# Zigbee.net
KiCad netlist of a schematic drawn in Altium Designer
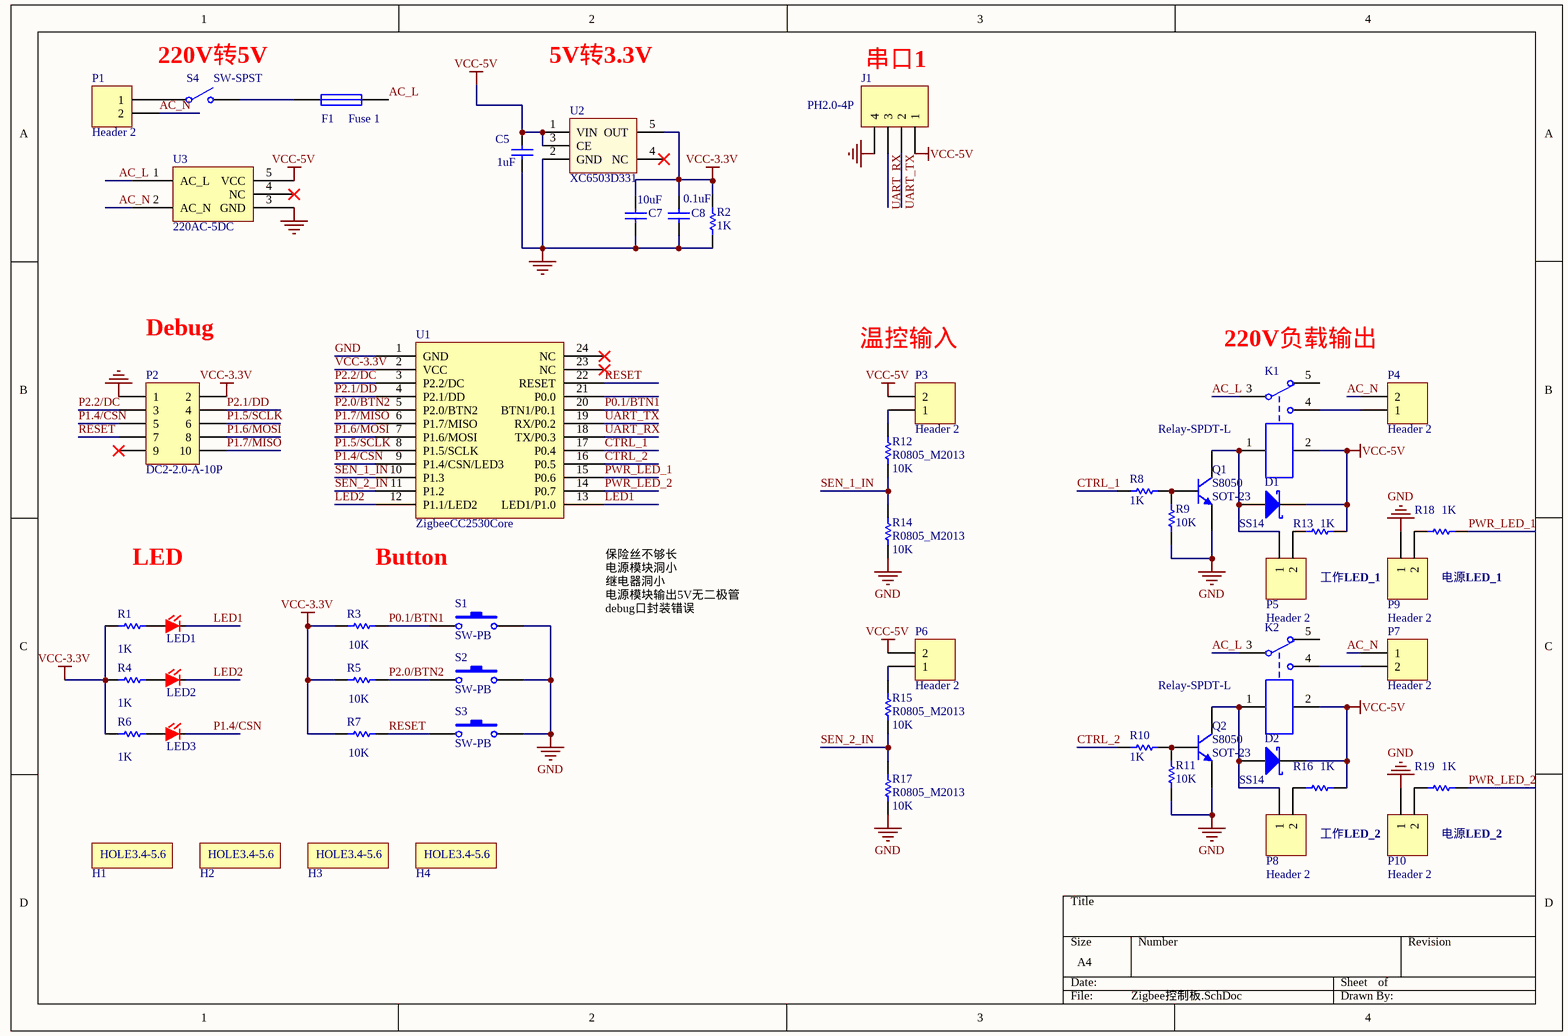
[diagram p0: Zigbee控制板.SchDoc]

(export (version "E")
  (design (tool "Eeschema 10.0.6"))
  (components
    (comp (ref "C5")
      (value "1uF")
      (footprint "C0805_M2013")
      (description "Capacitor")
      (fields (field (name "PUBLISHER") "Altium Limited"))
      (libsource (lib "Miscellaneous Devices") (part "Cap"))
    )
    (comp (ref "C7")
      (value "10uF")
      (footprint "C0805_M2013")
      (description "Capacitor")
      (fields (field (name "PUBLISHER") "Altium Limited"))
      (libsource (lib "Miscellaneous Devices") (part "Cap"))
    )
    (comp (ref "C8")
      (value "0.1uF")
      (footprint "C0805_M2013")
      (description "Capacitor")
      (fields (field (name "PUBLISHER") "Altium Limited"))
      (libsource (lib "Miscellaneous Devices") (part "Cap"))
    )
    (comp (ref "D1")
      (value "SS14")
      (footprint "SMA DO-214AC")
      (description "1.0 A Schottky Barrier Rectifiers")
      (fields (field (name "Comment") "SMA DO-214AC"))
      (libsource (lib "2.二极管原理库") (part "SS14"))
    )
    (comp (ref "D2")
      (value "SS14")
      (footprint "SMA DO-214AC")
      (description "1.0 A Schottky Barrier Rectifiers")
      (fields (field (name "Comment") "SMA DO-214AC"))
      (libsource (lib "2.二极管原理库") (part "SS14"))
    )
    (comp (ref "F1")
      (value "Fuse 1")
      (footprint "POLAR0.8")
      (description "Fuse")
      (fields (field (name "PUBLISHER") "Altium Limited"))
      (libsource (lib "Miscellaneous Devices") (part "Fuse 1"))
    )
    (comp (ref "H1")
      (value "HOLE3.4-5.6")
      (footprint "HOLE3.4-5.6")
      (libsource (lib "6.模块封装、Mark点、定位孔") (part "HOLE3.4-5.6"))
    )
    (comp (ref "H2")
      (value "HOLE3.4-5.6")
      (footprint "HOLE3.4-5.6")
      (libsource (lib "6.模块封装、Mark点、定位孔") (part "HOLE3.4-5.6"))
    )
    (comp (ref "H3")
      (value "HOLE3.4-5.6")
      (footprint "HOLE3.4-5.6")
      (libsource (lib "6.模块封装、Mark点、定位孔") (part "HOLE3.4-5.6"))
    )
    (comp (ref "H4")
      (value "HOLE3.4-5.6")
      (footprint "HOLE3.4-5.6")
      (libsource (lib "6.模块封装、Mark点、定位孔") (part "HOLE3.4-5.6"))
    )
    (comp (ref "J1")
      (value "PH2.0-4P")
      (footprint "PH2.0-4P")
      (description "Header, 4-Pin")
      (fields (field (name "PUBLISHER") "Altium Limited"))
      (libsource (lib "Miscellaneous Connectors") (part "Header 4"))
    )
    (comp (ref "K1")
      (value "Relay-SPDT-L")
      (footprint "Relay-SPDT-L")
      (description "Single-Pole Dual-Throw Relay")
      (fields (field (name "PUBLISHER") "Altium Limited"))
      (libsource (lib "Liyao原理图库") (part "Relay-SPDT-L"))
    )
    (comp (ref "K2")
      (value "Relay-SPDT-L")
      (footprint "Relay-SPDT-L")
      (description "Single-Pole Dual-Throw Relay")
      (fields (field (name "PUBLISHER") "Altium Limited"))
      (libsource (lib "Liyao原理图库") (part "Relay-SPDT-L"))
    )
    (comp (ref "LED1")
      (value "LED-R")
      (footprint "0805_LED")
      (description "LED红")
      (libsource (lib "Liyao原理图库") (part "LED-R"))
    )
    (comp (ref "LED2")
      (value "LED-R")
      (footprint "0805_LED")
      (description "LED红")
      (libsource (lib "Liyao原理图库") (part "LED-R"))
    )
    (comp (ref "LED3")
      (value "LED-R")
      (footprint "0805_LED")
      (description "LED红")
      (libsource (lib "Liyao原理图库") (part "LED-R"))
    )
    (comp (ref "P1")
      (value "Header 2")
      (footprint "KF301-2P")
      (description "Header, 2-Pin")
      (fields (field (name "PUBLISHER") "Altium Limited"))
      (libsource (lib "") (part "Header 2_3"))
    )
    (comp (ref "P2")
      (value "DC2-2.0-A-10P")
      (footprint "DC3-2.0-A-10P")
      (description "牛角座2.0 直插")
      (libsource (lib "8.其他连接器原理库") (part "DC2-2.0-A-10P"))
    )
    (comp (ref "P3")
      (value "Header 2")
      (footprint "HDR1X2")
      (description "Header, 2-Pin")
      (fields (field (name "PUBLISHER") "Altium Limited"))
      (libsource (lib "") (part "Header 2_1"))
    )
    (comp (ref "P4")
      (value "Header 2")
      (footprint "KF301-2P")
      (description "Header, 2-Pin")
      (fields (field (name "PUBLISHER") "Altium Limited"))
      (libsource (lib "") (part "Header 2_1"))
    )
    (comp (ref "P5")
      (value "Header 2")
      (footprint "HDR1X2")
      (description "Header, 2-Pin")
      (fields (field (name "PUBLISHER") "Altium Limited"))
      (libsource (lib "Miscellaneous Connectors") (part "Header 2"))
    )
    (comp (ref "P6")
      (value "Header 2")
      (footprint "HDR1X2")
      (description "Header, 2-Pin")
      (fields (field (name "PUBLISHER") "Altium Limited"))
      (libsource (lib "") (part "Header 2_1"))
    )
    (comp (ref "P7")
      (value "Header 2")
      (footprint "KF301-2P")
      (description "Header, 2-Pin")
      (fields (field (name "PUBLISHER") "Altium Limited"))
      (libsource (lib "") (part "Header 2_2"))
    )
    (comp (ref "P8")
      (value "Header 2")
      (footprint "HDR1X2")
      (description "Header, 2-Pin")
      (fields (field (name "PUBLISHER") "Altium Limited"))
      (libsource (lib "Miscellaneous Connectors") (part "Header 2"))
    )
    (comp (ref "P9")
      (value "Header 2")
      (footprint "HDR1X2")
      (description "Header, 2-Pin")
      (fields (field (name "PUBLISHER") "Altium Limited"))
      (libsource (lib "Miscellaneous Connectors") (part "Header 2"))
    )
    (comp (ref "P10")
      (value "Header 2")
      (footprint "HDR1X2")
      (description "Header, 2-Pin")
      (fields (field (name "PUBLISHER") "Altium Limited"))
      (libsource (lib "Miscellaneous Connectors") (part "Header 2"))
    )
    (comp (ref "Q1")
      (value "SOT-23")
      (footprint "SOT-23-3")
      (description "NPN Bipolar Transistor")
      (fields (field (name "ALTIUM_VALUE") "S8050") (field (name "PUBLISHER") "Altium Limited"))
      (libsource (lib "CYSchlib") (part "NPN"))
    )
    (comp (ref "Q2")
      (value "SOT-23")
      (footprint "SOT-23-3")
      (description "NPN Bipolar Transistor")
      (fields (field (name "ALTIUM_VALUE") "S8050") (field (name "PUBLISHER") "Altium Limited"))
      (libsource (lib "CYSchlib") (part "NPN"))
    )
    (comp (ref "R1")
      (value "1K")
      (footprint "R0805_M2013")
      (description "Resistor")
      (fields (field (name "Comment") "R0805_M2013"))
      (libsource (lib "1.电阻、电容、电感原理库") (part "R0805_M2013"))
    )
    (comp (ref "R2")
      (value "1K")
      (footprint "R0805_M2013")
      (description "Resistor")
      (fields (field (name "PUBLISHER") "Altium Limited"))
      (libsource (lib "Miscellaneous Devices") (part "Res1"))
    )
    (comp (ref "R3")
      (value "10K")
      (footprint "R0805_M2013")
      (description "Resistor")
      (fields (field (name "Comment") "R0805_M2013"))
      (libsource (lib "1.电阻、电容、电感原理库") (part "R0805_M2013"))
    )
    (comp (ref "R4")
      (value "1K")
      (footprint "R0805_M2013")
      (description "Resistor")
      (fields (field (name "Comment") "R0805_M2013"))
      (libsource (lib "1.电阻、电容、电感原理库") (part "R0805_M2013"))
    )
    (comp (ref "R5")
      (value "10K")
      (footprint "R0805_M2013")
      (description "Resistor")
      (fields (field (name "Comment") "R0805_M2013"))
      (libsource (lib "1.电阻、电容、电感原理库") (part "R0805_M2013"))
    )
    (comp (ref "R6")
      (value "1K")
      (footprint "R0805_M2013")
      (description "Resistor")
      (fields (field (name "Comment") "R0805_M2013"))
      (libsource (lib "1.电阻、电容、电感原理库") (part "R0805_M2013"))
    )
    (comp (ref "R7")
      (value "10K")
      (footprint "R0805_M2013")
      (description "Resistor")
      (fields (field (name "Comment") "R0805_M2013"))
      (libsource (lib "1.电阻、电容、电感原理库") (part "R0805_M2013"))
    )
    (comp (ref "R8")
      (value "1K")
      (footprint "R0805_M2013")
      (description "Resistor")
      (fields (field (name "PUBLISHER") "Altium Limited"))
      (libsource (lib "Miscellaneous Devices") (part "Res1"))
    )
    (comp (ref "R9")
      (value "10K")
      (footprint "R0805_M2013")
      (description "Resistor")
      (fields (field (name "PUBLISHER") "Altium Limited"))
      (libsource (lib "Miscellaneous Devices") (part "Res1"))
    )
    (comp (ref "R10")
      (value "1K")
      (footprint "R0805_M2013")
      (description "Resistor")
      (fields (field (name "PUBLISHER") "Altium Limited"))
      (libsource (lib "Miscellaneous Devices") (part "Res1"))
    )
    (comp (ref "R11")
      (value "10K")
      (footprint "R0805_M2013")
      (description "Resistor")
      (fields (field (name "PUBLISHER") "Altium Limited"))
      (libsource (lib "Miscellaneous Devices") (part "Res1"))
    )
    (comp (ref "R12")
      (value "R0805_M2013")
      (footprint "R0805_M2013")
      (description "Resistor")
      (fields (field (name "ALTIUM_VALUE") "10K"))
      (libsource (lib "1.电阻、电容、电感原理库") (part "R0805_M2013"))
    )
    (comp (ref "R13")
      (value "1K")
      (footprint "R0805_M2013")
      (description "Resistor")
      (fields (field (name "Comment") "R0805_M2013"))
      (libsource (lib "1.电阻、电容、电感原理库") (part "R0805_M2013"))
    )
    (comp (ref "R14")
      (value "R0805_M2013")
      (footprint "R0805_M2013")
      (description "Resistor")
      (fields (field (name "ALTIUM_VALUE") "10K"))
      (libsource (lib "1.电阻、电容、电感原理库") (part "R0805_M2013"))
    )
    (comp (ref "R15")
      (value "R0805_M2013")
      (footprint "R0805_M2013")
      (description "Resistor")
      (fields (field (name "ALTIUM_VALUE") "10K"))
      (libsource (lib "1.电阻、电容、电感原理库") (part "R0805_M2013"))
    )
    (comp (ref "R16")
      (value "1K")
      (footprint "R0805_M2013")
      (description "Resistor")
      (fields (field (name "Comment") "R0805_M2013"))
      (libsource (lib "1.电阻、电容、电感原理库") (part "R0805_M2013"))
    )
    (comp (ref "R17")
      (value "R0805_M2013")
      (footprint "R0805_M2013")
      (description "Resistor")
      (fields (field (name "ALTIUM_VALUE") "10K"))
      (libsource (lib "1.电阻、电容、电感原理库") (part "R0805_M2013"))
    )
    (comp (ref "R18")
      (value "1K")
      (footprint "R0805_M2013")
      (description "Resistor")
      (fields (field (name "Comment") "R0805_M2013"))
      (libsource (lib "1.电阻、电容、电感原理库") (part "R0805_M2013"))
    )
    (comp (ref "R19")
      (value "1K")
      (footprint "R0805_M2013")
      (description "Resistor")
      (fields (field (name "Comment") "R0805_M2013"))
      (libsource (lib "1.电阻、电容、电感原理库") (part "R0805_M2013"))
    )
    (comp (ref "S1")
      (value "SW-PB")
      (footprint "SW-KEY")
      (description "Switch")
      (fields (field (name "PUBLISHER") "Altium Limited"))
      (libsource (lib "Miscellaneous Devices") (part "SW-PB"))
    )
    (comp (ref "S2")
      (value "SW-PB")
      (footprint "SW-KEY")
      (description "Switch")
      (fields (field (name "PUBLISHER") "Altium Limited"))
      (libsource (lib "Miscellaneous Devices") (part "SW-PB"))
    )
    (comp (ref "S3")
      (value "SW-PB")
      (footprint "SW-KEY")
      (description "Switch")
      (fields (field (name "PUBLISHER") "Altium Limited"))
      (libsource (lib "Miscellaneous Devices") (part "SW-PB"))
    )
    (comp (ref "S4")
      (value "SW-SPST")
      (footprint "SW-SHIP")
      (description "Single-Pole, Single-Throw Switch")
      (fields (field (name "PUBLISHER") "Altium Limited"))
      (libsource (lib "Miscellaneous Devices") (part "SW-SPST"))
    )
    (comp (ref "U1")
      (value "ZigbeeCC2530Core")
      (footprint "CC2530_CORE")
      (libsource (lib "Liyao原理图库") (part "ZigbeeCC2530Core"))
    )
    (comp (ref "U2")
      (value "XC6503D331")
      (footprint "SOT23-5")
      (libsource (lib "CYSchlib") (part "XC6503Dxxx"))
    )
    (comp (ref "U3")
      (value "220AC-5DC")
      (footprint "220AC-5DC")
      (description "220VAC转5VDC模块")
      (libsource (lib "Liyao原理图库") (part "220AC-5DC"))
    )
  )
  (nets
    (net (code "1") (name "/AC_L") (class "Default")
      (node (ref "F1") (pin "2") (pinfunction "2_2") (pintype "passive"))
      (node (ref "K1") (pin "3") (pinfunction "3_3") (pintype "passive"))
      (node (ref "K2") (pin "3") (pinfunction "3_3") (pintype "passive"))
      (node (ref "U3") (pin "1") (pinfunction "AC_L_1") (pintype "passive"))
    )
    (net (code "2") (name "/AC_N") (class "Default")
      (node (ref "P1") (pin "2") (pinfunction "2_2") (pintype "passive"))
      (node (ref "P4") (pin "2") (pinfunction "2_2") (pintype "passive"))
      (node (ref "P7") (pin "1") (pinfunction "1_1") (pintype "passive"))
      (node (ref "U3") (pin "2") (pinfunction "AC_N_2") (pintype "passive"))
    )
    (net (code "3") (name "/CTRL_1") (class "Default")
      (node (ref "R8") (pin "2") (pinfunction "2_2") (pintype "passive"))
      (node (ref "U1") (pin "17") (pinfunction "P0.4_17") (pintype "passive"))
    )
    (net (code "4") (name "/CTRL_2") (class "Default")
      (node (ref "R10") (pin "2") (pinfunction "2_2") (pintype "passive"))
      (node (ref "U1") (pin "16") (pinfunction "P0.5_16") (pintype "passive"))
    )
    (net (code "5") (name "/LED1") (class "Default")
      (node (ref "LED1") (pin "2") (pinfunction "2_2") (pintype "passive"))
      (node (ref "U1") (pin "13") (pinfunction "LED1/P1.0_13") (pintype "passive"))
    )
    (net (code "6") (name "/LED2") (class "Default")
      (node (ref "LED2") (pin "2") (pinfunction "2_2") (pintype "passive"))
      (node (ref "U1") (pin "12") (pinfunction "P1.1/LED2_12") (pintype "passive"))
    )
    (net (code "7") (name "/P0.1{slash}BTN1") (class "Default")
      (node (ref "R3") (pin "2") (pinfunction "2_2") (pintype "passive"))
      (node (ref "S1") (pin "1") (pinfunction "1_1") (pintype "passive"))
      (node (ref "U1") (pin "20") (pinfunction "BTN1/P0.1_20") (pintype "passive"))
    )
    (net (code "8") (name "/P1.4{slash}CSN") (class "Default")
      (node (ref "LED3") (pin "2") (pinfunction "2_2") (pintype "passive"))
      (node (ref "P2") (pin "5") (pinfunction "5_5") (pintype "passive"))
      (node (ref "U1") (pin "9") (pinfunction "P1.4/CSN/LED3_9") (pintype "passive"))
    )
    (net (code "9") (name "/P1.5{slash}SCLK") (class "Default")
      (node (ref "P2") (pin "6") (pinfunction "6_6") (pintype "passive"))
      (node (ref "U1") (pin "8") (pinfunction "P1.5/SCLK_8") (pintype "passive"))
    )
    (net (code "10") (name "/P1.6{slash}MOSI") (class "Default")
      (node (ref "P2") (pin "8") (pinfunction "8_8") (pintype "passive"))
      (node (ref "U1") (pin "7") (pinfunction "P1.6/MOSI_7") (pintype "passive"))
    )
    (net (code "11") (name "/P1.7{slash}MISO") (class "Default")
      (node (ref "P2") (pin "10") (pinfunction "10_10") (pintype "passive"))
      (node (ref "U1") (pin "6") (pinfunction "P1.7/MISO_6") (pintype "passive"))
    )
    (net (code "12") (name "/P2.0{slash}BTN2") (class "Default")
      (node (ref "R5") (pin "2") (pinfunction "2_2") (pintype "passive"))
      (node (ref "S2") (pin "1") (pinfunction "1_1") (pintype "passive"))
      (node (ref "U1") (pin "5") (pinfunction "P2.0/BTN2_5") (pintype "passive"))
    )
    (net (code "13") (name "/P2.1{slash}DD") (class "Default")
      (node (ref "P2") (pin "4") (pinfunction "4_4") (pintype "passive"))
      (node (ref "U1") (pin "4") (pinfunction "P2.1/DD_4") (pintype "passive"))
    )
    (net (code "14") (name "/P2.2{slash}DC") (class "Default")
      (node (ref "P2") (pin "3") (pinfunction "3_3") (pintype "passive"))
      (node (ref "U1") (pin "3") (pinfunction "P2.2/DC_3") (pintype "passive"))
    )
    (net (code "15") (name "/PWR_LED_1") (class "Default")
      (node (ref "R18") (pin "1") (pinfunction "1_1") (pintype "passive"))
      (node (ref "U1") (pin "15") (pinfunction "P0.6_15") (pintype "passive"))
    )
    (net (code "16") (name "/PWR_LED_2") (class "Default")
      (node (ref "R19") (pin "1") (pinfunction "1_1") (pintype "passive"))
      (node (ref "U1") (pin "14") (pinfunction "P0.7_14") (pintype "passive"))
    )
    (net (code "17") (name "/RESET") (class "Default")
      (node (ref "P2") (pin "7") (pinfunction "7_7") (pintype "passive"))
      (node (ref "R7") (pin "2") (pinfunction "2_2") (pintype "passive"))
      (node (ref "S3") (pin "1") (pinfunction "1_1") (pintype "passive"))
      (node (ref "U1") (pin "22") (pinfunction "RESET_22") (pintype "passive"))
    )
    (net (code "18") (name "/SEN_1_IN") (class "Default")
      (node (ref "R12") (pin "1") (pinfunction "1_1") (pintype "passive"))
      (node (ref "R14") (pin "2") (pinfunction "2_2") (pintype "passive"))
      (node (ref "U1") (pin "10") (pinfunction "P1.3_10") (pintype "passive"))
    )
    (net (code "19") (name "/SEN_2_IN") (class "Default")
      (node (ref "R15") (pin "1") (pinfunction "1_1") (pintype "passive"))
      (node (ref "R17") (pin "2") (pinfunction "2_2") (pintype "passive"))
      (node (ref "U1") (pin "11") (pinfunction "P1.2_11") (pintype "passive"))
    )
    (net (code "20") (name "/UART_RX") (class "Default")
      (node (ref "J1") (pin "3") (pinfunction "3_3") (pintype "passive"))
      (node (ref "U1") (pin "18") (pinfunction "TX/P0.3_18") (pintype "passive"))
    )
    (net (code "21") (name "/UART_TX") (class "Default")
      (node (ref "J1") (pin "2") (pinfunction "2_2") (pintype "passive"))
      (node (ref "U1") (pin "19") (pinfunction "RX/P0.2_19") (pintype "passive"))
    )
    (net (code "22") (name "GND") (class "Default")
      (node (ref "C5") (pin "1") (pinfunction "1_1") (pintype "passive"))
      (node (ref "C7") (pin "2") (pinfunction "2_2") (pintype "passive"))
      (node (ref "C8") (pin "2") (pinfunction "2_2") (pintype "passive"))
      (node (ref "J1") (pin "4") (pinfunction "4_4") (pintype "passive"))
      (node (ref "P10") (pin "1") (pinfunction "1_1") (pintype "passive"))
      (node (ref "P2") (pin "1") (pinfunction "1_1") (pintype "passive"))
      (node (ref "P9") (pin "1") (pinfunction "1_1") (pintype "passive"))
      (node (ref "Q1") (pin "2") (pinfunction "E_2") (pintype "passive"))
      (node (ref "Q2") (pin "2") (pinfunction "E_2") (pintype "passive"))
      (node (ref "R11") (pin "1") (pinfunction "1_1") (pintype "passive"))
      (node (ref "R14") (pin "1") (pinfunction "1_1") (pintype "passive"))
      (node (ref "R17") (pin "1") (pinfunction "1_1") (pintype "passive"))
      (node (ref "R2") (pin "1") (pinfunction "1_1") (pintype "passive"))
      (node (ref "R9") (pin "1") (pinfunction "1_1") (pintype "passive"))
      (node (ref "S1") (pin "2") (pinfunction "2_2") (pintype "passive"))
      (node (ref "S2") (pin "2") (pinfunction "2_2") (pintype "passive"))
      (node (ref "S3") (pin "2") (pinfunction "2_2") (pintype "passive"))
      (node (ref "U1") (pin "1") (pinfunction "GND_1") (pintype "passive"))
      (node (ref "U2") (pin "2") (pinfunction "GND_2") (pintype "passive"))
      (node (ref "U3") (pin "3") (pinfunction "GND_3") (pintype "passive"))
    )
    (net (code "23") (name "Net-(D1-A)") (class "Default")
      (node (ref "D1") (pin "1") (pinfunction "A_1") (pintype "passive"))
      (node (ref "K1") (pin "1") (pinfunction "1_1") (pintype "passive"))
      (node (ref "P5") (pin "1") (pinfunction "1_1") (pintype "passive"))
      (node (ref "Q1") (pin "3") (pinfunction "C_3") (pintype "passive"))
    )
    (net (code "24") (name "Net-(D2-A)") (class "Default")
      (node (ref "D2") (pin "1") (pinfunction "A_1") (pintype "passive"))
      (node (ref "K2") (pin "1") (pinfunction "1_1") (pintype "passive"))
      (node (ref "P8") (pin "1") (pinfunction "1_1") (pintype "passive"))
      (node (ref "Q2") (pin "3") (pinfunction "C_3") (pintype "passive"))
    )
    (net (code "25") (name "Net-(K1-Pad4)") (class "Default")
      (node (ref "K1") (pin "4") (pinfunction "4_4") (pintype "passive"))
      (node (ref "P4") (pin "1") (pinfunction "1_1") (pintype "passive"))
    )
    (net (code "26") (name "Net-(K2-Pad4)") (class "Default")
      (node (ref "K2") (pin "4") (pinfunction "4_4") (pintype "passive"))
      (node (ref "P7") (pin "2") (pinfunction "2_2") (pintype "passive"))
    )
    (net (code "27") (name "Net-(LED1-Pad1)") (class "Default")
      (node (ref "LED1") (pin "1") (pinfunction "1_1") (pintype "passive"))
      (node (ref "R1") (pin "2") (pinfunction "2_2") (pintype "passive"))
    )
    (net (code "28") (name "Net-(LED2-Pad1)") (class "Default")
      (node (ref "LED2") (pin "1") (pinfunction "1_1") (pintype "passive"))
      (node (ref "R4") (pin "2") (pinfunction "2_2") (pintype "passive"))
    )
    (net (code "29") (name "Net-(LED3-Pad1)") (class "Default")
      (node (ref "LED3") (pin "1") (pinfunction "1_1") (pintype "passive"))
      (node (ref "R6") (pin "2") (pinfunction "2_2") (pintype "passive"))
    )
    (net (code "30") (name "Net-(P3-Pad1)") (class "Default")
      (node (ref "P3") (pin "1") (pinfunction "1_1") (pintype "passive"))
      (node (ref "R12") (pin "2") (pinfunction "2_2") (pintype "passive"))
    )
    (net (code "31") (name "Net-(P5-Pad2)") (class "Default")
      (node (ref "P5") (pin "2") (pinfunction "2_2") (pintype "passive"))
      (node (ref "R13") (pin "2") (pinfunction "2_2") (pintype "passive"))
    )
    (net (code "32") (name "Net-(P6-Pad1)") (class "Default")
      (node (ref "P6") (pin "1") (pinfunction "1_1") (pintype "passive"))
      (node (ref "R15") (pin "2") (pinfunction "2_2") (pintype "passive"))
    )
    (net (code "33") (name "Net-(P8-Pad2)") (class "Default")
      (node (ref "P8") (pin "2") (pinfunction "2_2") (pintype "passive"))
      (node (ref "R16") (pin "2") (pinfunction "2_2") (pintype "passive"))
    )
    (net (code "34") (name "Net-(P9-Pad2)") (class "Default")
      (node (ref "P9") (pin "2") (pinfunction "2_2") (pintype "passive"))
      (node (ref "R18") (pin "2") (pinfunction "2_2") (pintype "passive"))
    )
    (net (code "35") (name "Net-(P10-Pad2)") (class "Default")
      (node (ref "P10") (pin "2") (pinfunction "2_2") (pintype "passive"))
      (node (ref "R19") (pin "2") (pinfunction "2_2") (pintype "passive"))
    )
    (net (code "36") (name "Net-(Q1-B)") (class "Default")
      (node (ref "Q1") (pin "1") (pinfunction "B_1") (pintype "passive"))
      (node (ref "R8") (pin "1") (pinfunction "1_1") (pintype "passive"))
      (node (ref "R9") (pin "2") (pinfunction "2_2") (pintype "passive"))
    )
    (net (code "37") (name "Net-(Q2-B)") (class "Default")
      (node (ref "Q2") (pin "1") (pinfunction "B_1") (pintype "passive"))
      (node (ref "R10") (pin "1") (pinfunction "1_1") (pintype "passive"))
      (node (ref "R11") (pin "2") (pinfunction "2_2") (pintype "passive"))
    )
    (net (code "38") (name "Net-(S4-COMMON)") (class "Default")
      (node (ref "P1") (pin "1") (pinfunction "1_1") (pintype "passive"))
      (node (ref "S4") (pin "1") (pinfunction "COMMON_1") (pintype "passive"))
    )
    (net (code "39") (name "Net-(S4-NO)") (class "Default")
      (node (ref "F1") (pin "1") (pinfunction "1_1") (pintype "passive"))
      (node (ref "S4") (pin "2") (pinfunction "NO_2") (pintype "passive"))
    )
    (net (code "40") (name "VCC-3.3V") (class "Default")
      (node (ref "C7") (pin "1") (pinfunction "1_1") (pintype "passive"))
      (node (ref "C8") (pin "1") (pinfunction "1_1") (pintype "passive"))
      (node (ref "P2") (pin "2") (pinfunction "2_2") (pintype "passive"))
      (node (ref "R1") (pin "1") (pinfunction "1_1") (pintype "passive"))
      (node (ref "R2") (pin "2") (pinfunction "2_2") (pintype "passive"))
      (node (ref "R3") (pin "1") (pinfunction "1_1") (pintype "passive"))
      (node (ref "R4") (pin "1") (pinfunction "1_1") (pintype "passive"))
      (node (ref "R5") (pin "1") (pinfunction "1_1") (pintype "passive"))
      (node (ref "R6") (pin "1") (pinfunction "1_1") (pintype "passive"))
      (node (ref "R7") (pin "1") (pinfunction "1_1") (pintype "passive"))
      (node (ref "U1") (pin "2") (pinfunction "VCC_2") (pintype "passive"))
      (node (ref "U2") (pin "5") (pinfunction "OUT_5") (pintype "passive"))
    )
    (net (code "41") (name "VCC-5V") (class "Default")
      (node (ref "C5") (pin "2") (pinfunction "2_2") (pintype "passive"))
      (node (ref "D1") (pin "2") (pinfunction "K_2") (pintype "passive"))
      (node (ref "D2") (pin "2") (pinfunction "K_2") (pintype "passive"))
      (node (ref "J1") (pin "1") (pinfunction "1_1") (pintype "passive"))
      (node (ref "K1") (pin "2") (pinfunction "2_2") (pintype "passive"))
      (node (ref "K2") (pin "2") (pinfunction "2_2") (pintype "passive"))
      (node (ref "P3") (pin "2") (pinfunction "2_2") (pintype "passive"))
      (node (ref "P6") (pin "2") (pinfunction "2_2") (pintype "passive"))
      (node (ref "R13") (pin "1") (pinfunction "1_1") (pintype "passive"))
      (node (ref "R16") (pin "1") (pinfunction "1_1") (pintype "passive"))
      (node (ref "U2") (pin "1") (pinfunction "VIN_1") (pintype "passive"))
      (node (ref "U2") (pin "3") (pinfunction "CE_3") (pintype "passive"))
      (node (ref "U3") (pin "5") (pinfunction "VCC_5") (pintype "passive"))
    )
    (net (code "42") (name "unconnected-(K1-Pad5)") (class "Default")
      (node (ref "K1") (pin "5") (pinfunction "5_5") (pintype "passive"))
    )
    (net (code "43") (name "unconnected-(K2-Pad5)") (class "Default")
      (node (ref "K2") (pin "5") (pinfunction "5_5") (pintype "passive"))
    )
    (net (code "44") (name "unconnected-(P2-Pad9)") (class "Default")
      (node (ref "P2") (pin "9") (pinfunction "9_9") (pintype "passive+no_connect"))
    )
    (net (code "45") (name "unconnected-(U1-NC-Pad23)") (class "Default")
      (node (ref "U1") (pin "23") (pinfunction "NC_23") (pintype "passive+no_connect"))
    )
    (net (code "46") (name "unconnected-(U1-NC-Pad24)") (class "Default")
      (node (ref "U1") (pin "24") (pinfunction "NC_24") (pintype "passive+no_connect"))
    )
    (net (code "47") (name "unconnected-(U1-P0.0-Pad21)") (class "Default")
      (node (ref "U1") (pin "21") (pinfunction "P0.0_21") (pintype "passive"))
    )
    (net (code "48") (name "unconnected-(U2-NC-Pad4)") (class "Default")
      (node (ref "U2") (pin "4") (pinfunction "NC_4") (pintype "passive+no_connect"))
    )
    (net (code "49") (name "unconnected-(U3-NC-Pad4)") (class "Default")
      (node (ref "U3") (pin "4") (pinfunction "NC_4") (pintype "passive+no_connect"))
    )
  )
)
